# ARDUINO.net
KiCad netlist of a schematic drawn in Altium Designer
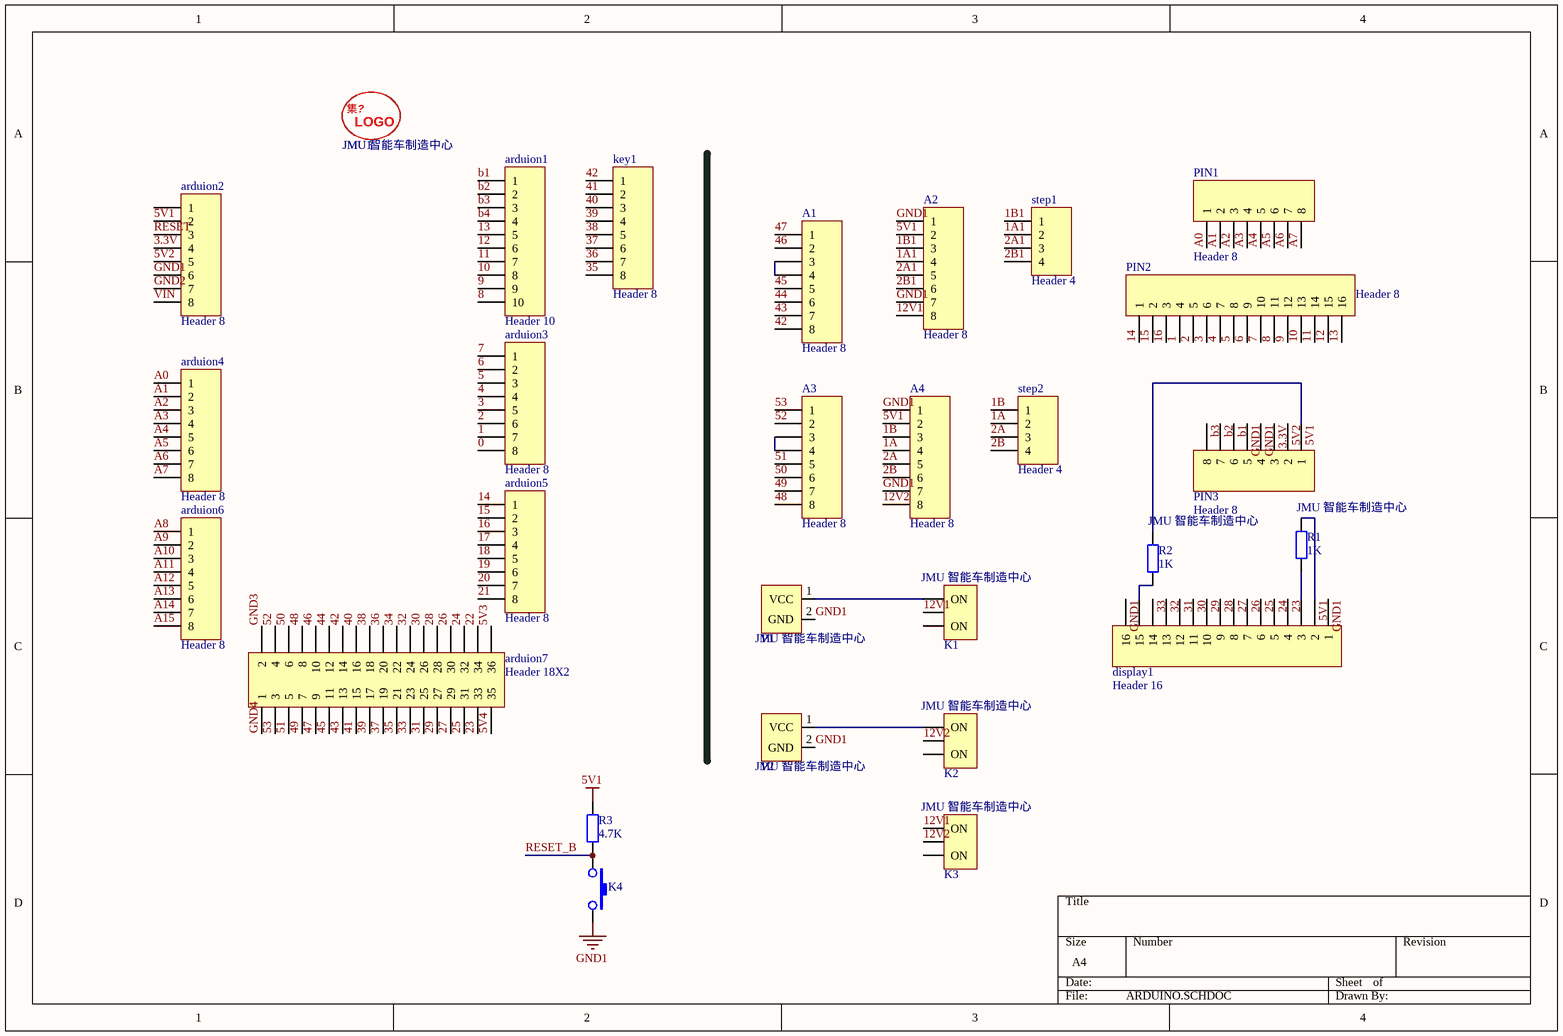
[diagram p0: ARDUINO.SCHDOC]

(export (version "E")
  (design (tool "Eeschema 10.0.6"))
  (components
    (comp (ref "A1")
      (value "Header 8")
      (footprint "HDR1X8")
      (description "Header, 8-Pin")
      (fields (field (name "PUBLISHER") "Altium Limited"))
      (libsource (lib "Miscellaneous Connectors") (part "Header 8"))
    )
    (comp (ref "A2")
      (value "Header 8")
      (footprint "HDR1X8")
      (description "Header, 8-Pin")
      (fields (field (name "PUBLISHER") "Altium Limited"))
      (libsource (lib "Miscellaneous Connectors") (part "Header 8"))
    )
    (comp (ref "A3")
      (value "Header 8")
      (footprint "HDR1X8")
      (description "Header, 8-Pin")
      (fields (field (name "PUBLISHER") "Altium Limited"))
      (libsource (lib "Miscellaneous Connectors") (part "Header 8"))
    )
    (comp (ref "A4")
      (value "Header 8")
      (footprint "HDR1X8")
      (description "Header, 8-Pin")
      (fields (field (name "PUBLISHER") "Altium Limited"))
      (libsource (lib "Miscellaneous Connectors") (part "Header 8"))
    )
    (comp (ref "arduion1")
      (value "Header 10")
      (footprint "HDR1X10")
      (description "Header, 10-Pin")
      (fields (field (name "PUBLISHER") "Altium Limited"))
      (libsource (lib "Miscellaneous Connectors") (part "Header 10"))
    )
    (comp (ref "arduion2")
      (value "Header 8")
      (footprint "HDR1X8")
      (description "Header, 8-Pin")
      (fields (field (name "PUBLISHER") "Altium Limited"))
      (libsource (lib "Miscellaneous Connectors") (part "Header 8"))
    )
    (comp (ref "arduion3")
      (value "Header 8")
      (footprint "HDR1X8")
      (description "Header, 8-Pin")
      (fields (field (name "PUBLISHER") "Altium Limited"))
      (libsource (lib "Miscellaneous Connectors") (part "Header 8"))
    )
    (comp (ref "arduion4")
      (value "Header 8")
      (footprint "HDR1X8")
      (description "Header, 8-Pin")
      (fields (field (name "PUBLISHER") "Altium Limited"))
      (libsource (lib "Miscellaneous Connectors") (part "Header 8"))
    )
    (comp (ref "arduion5")
      (value "Header 8")
      (footprint "HDR1X8")
      (description "Header, 8-Pin")
      (fields (field (name "PUBLISHER") "Altium Limited"))
      (libsource (lib "Miscellaneous Connectors") (part "Header 8"))
    )
    (comp (ref "arduion6")
      (value "Header 8")
      (footprint "HDR1X8")
      (description "Header, 8-Pin")
      (fields (field (name "PUBLISHER") "Altium Limited"))
      (libsource (lib "Miscellaneous Connectors") (part "Header 8"))
    )
    (comp (ref "arduion7")
      (value "Header 18X2")
      (footprint "HDR2X18")
      (description "Header, 18-Pin, Dual row")
      (fields (field (name "PUBLISHER") "Altium Limited"))
      (libsource (lib "Miscellaneous Connectors") (part "Header 18X2"))
    )
    (comp (ref "display1")
      (value "Header 16")
      (footprint "HDR1X16")
      (description "Header, 16-Pin")
      (fields (field (name "PUBLISHER") "Altium Limited"))
      (libsource (lib "Miscellaneous Connectors") (part "Header 16"))
    )
    (comp (ref "JMU1")
      (value "JMU")
      (footprint "JMU_logo（1）")
      (libsource (lib "JMU智能车专用3.0.6") (part "JMU-LOGO"))
    )
    (comp (ref "K1")
      (value "KEY")
      (footprint "钮子开关（大）")
      (description "AC 250V/6A")
      (libsource (lib "JMU智能车专用3.0.6") (part "钮子开关（大）"))
    )
    (comp (ref "K2")
      (value "KEY")
      (footprint "钮子开关（大）")
      (description "AC 250V/6A")
      (libsource (lib "JMU智能车专用3.0.6") (part "钮子开关（大）"))
    )
    (comp (ref "K3")
      (value "KEY")
      (footprint "钮子开关（大）")
      (description "AC 250V/6A")
      (libsource (lib "JMU智能车专用3.0.6") (part "钮子开关（大）"))
    )
    (comp (ref "K4")
      (value "RESET")
      (footprint "SW_PB2_A1")
      (description "按键")
      (libsource (lib "Bigbear") (part "KEY"))
    )
    (comp (ref "key1")
      (value "Header 8")
      (footprint "HDR1X8")
      (description "Header, 8-Pin")
      (fields (field (name "PUBLISHER") "Altium Limited"))
      (libsource (lib "Miscellaneous Connectors") (part "Header 8"))
    )
    (comp (ref "P1")
      (value "T头")
      (footprint "T型接头")
      (description "T型头")
      (libsource (lib "JMU智能车专用3.0.6") (part "电源接线端子"))
    )
    (comp (ref "P2")
      (value "T头")
      (footprint "T型接头")
      (description "T型头")
      (libsource (lib "JMU智能车专用3.0.6") (part "电源接线端子"))
    )
    (comp (ref "PIN1")
      (value "Header 8")
      (footprint "HDR1X8")
      (description "Header, 8-Pin")
      (fields (field (name "PUBLISHER") "Altium Limited"))
      (libsource (lib "") (part "Header 8_1"))
    )
    (comp (ref "PIN2")
      (value "Header 8")
      (footprint "HDR1X16")
      (description "Header, 16-Pin")
      (fields (field (name "PUBLISHER") "Altium Limited"))
      (libsource (lib "") (part "Header 16_1"))
    )
    (comp (ref "PIN3")
      (value "Header 8")
      (footprint "HDR1X8")
      (description "Header, 8-Pin")
      (fields (field (name "PUBLISHER") "Altium Limited"))
      (libsource (lib "") (part "Header 8_2"))
    )
    (comp (ref "R1")
      (value "1K")
      (footprint "0603")
      (description "通用电阻")
      (libsource (lib "JMU智能车专用3.0.6") (part "Res"))
    )
    (comp (ref "R2")
      (value "1K")
      (footprint "0603")
      (description "通用电阻")
      (libsource (lib "JMU智能车专用3.0.6") (part "Res"))
    )
    (comp (ref "R3") (value "4.7K") (footprint "0603-r") (libsource (lib "Bigbear") (part "RES")))
    (comp (ref "step1")
      (value "Header 4")
      (footprint "HDR1X4")
      (description "Header, 4-Pin")
      (fields (field (name "PUBLISHER") "Altium Limited"))
      (libsource (lib "Miscellaneous Connectors") (part "Header 4"))
    )
    (comp (ref "step2")
      (value "Header 4")
      (footprint "HDR1X4")
      (description "Header, 4-Pin")
      (fields (field (name "PUBLISHER") "Altium Limited"))
      (libsource (lib "Miscellaneous Connectors") (part "Header 4"))
    )
  )
  (nets
    (net (code "1") (name "/0") (class "Default")
      (node (ref "arduion3") (pin "8") (pinfunction "8_8") (pintype "passive"))
    )
    (net (code "2") (name "/1") (class "Default")
      (node (ref "PIN2") (pin "4") (pinfunction "4_4") (pintype "passive"))
      (node (ref "arduion3") (pin "7") (pinfunction "7_7") (pintype "passive"))
    )
    (net (code "3") (name "/1A") (class "Default")
      (node (ref "A4") (pin "4") (pinfunction "4_4") (pintype "passive"))
      (node (ref "step2") (pin "2") (pinfunction "2_2") (pintype "passive"))
    )
    (net (code "4") (name "/1A1") (class "Default")
      (node (ref "A2") (pin "4") (pinfunction "4_4") (pintype "passive"))
      (node (ref "step1") (pin "2") (pinfunction "2_2") (pintype "passive"))
    )
    (net (code "5") (name "/1B") (class "Default")
      (node (ref "A4") (pin "3") (pinfunction "3_3") (pintype "passive"))
      (node (ref "step2") (pin "1") (pinfunction "1_1") (pintype "passive"))
    )
    (net (code "6") (name "/1B1") (class "Default")
      (node (ref "A2") (pin "3") (pinfunction "3_3") (pintype "passive"))
      (node (ref "step1") (pin "1") (pinfunction "1_1") (pintype "passive"))
    )
    (net (code "7") (name "/2") (class "Default")
      (node (ref "PIN2") (pin "5") (pinfunction "5_5") (pintype "passive"))
      (node (ref "arduion3") (pin "6") (pinfunction "6_6") (pintype "passive"))
    )
    (net (code "8") (name "/2A") (class "Default")
      (node (ref "A4") (pin "5") (pinfunction "5_5") (pintype "passive"))
      (node (ref "step2") (pin "3") (pinfunction "3_3") (pintype "passive"))
    )
    (net (code "9") (name "/2A1") (class "Default")
      (node (ref "A2") (pin "5") (pinfunction "5_5") (pintype "passive"))
      (node (ref "step1") (pin "3") (pinfunction "3_3") (pintype "passive"))
    )
    (net (code "10") (name "/2B") (class "Default")
      (node (ref "A4") (pin "6") (pinfunction "6_6") (pintype "passive"))
      (node (ref "step2") (pin "4") (pinfunction "4_4") (pintype "passive"))
    )
    (net (code "11") (name "/2B1") (class "Default")
      (node (ref "A2") (pin "6") (pinfunction "6_6") (pintype "passive"))
      (node (ref "step1") (pin "4") (pinfunction "4_4") (pintype "passive"))
    )
    (net (code "12") (name "/3") (class "Default")
      (node (ref "PIN2") (pin "6") (pinfunction "6_6") (pintype "passive"))
      (node (ref "arduion3") (pin "5") (pinfunction "5_5") (pintype "passive"))
    )
    (net (code "13") (name "/3.3V") (class "Default")
      (node (ref "PIN3") (pin "3") (pinfunction "3_3") (pintype "passive"))
      (node (ref "arduion2") (pin "4") (pinfunction "4_4") (pintype "passive"))
    )
    (net (code "14") (name "/4") (class "Default")
      (node (ref "PIN2") (pin "7") (pinfunction "7_7") (pintype "passive"))
      (node (ref "arduion3") (pin "4") (pinfunction "4_4") (pintype "passive"))
    )
    (net (code "15") (name "/5") (class "Default")
      (node (ref "PIN2") (pin "8") (pinfunction "8_8") (pintype "passive"))
      (node (ref "arduion3") (pin "3") (pinfunction "3_3") (pintype "passive"))
    )
    (net (code "16") (name "/5V2") (class "Default")
      (node (ref "PIN3") (pin "2") (pinfunction "2_2") (pintype "passive"))
      (node (ref "arduion2") (pin "5") (pinfunction "5_5") (pintype "passive"))
    )
    (net (code "17") (name "/5V3") (class "Default")
      (node (ref "arduion7") (pin "36") (pinfunction "36_36") (pintype "passive"))
    )
    (net (code "18") (name "/5V4") (class "Default")
      (node (ref "arduion7") (pin "35") (pinfunction "35_35") (pintype "passive"))
    )
    (net (code "19") (name "/6") (class "Default")
      (node (ref "PIN2") (pin "9") (pinfunction "9_9") (pintype "passive"))
      (node (ref "arduion3") (pin "2") (pinfunction "2_2") (pintype "passive"))
    )
    (net (code "20") (name "/7") (class "Default")
      (node (ref "PIN2") (pin "10") (pinfunction "10_10") (pintype "passive"))
      (node (ref "arduion3") (pin "1") (pinfunction "1_1") (pintype "passive"))
    )
    (net (code "21") (name "/8") (class "Default")
      (node (ref "PIN2") (pin "11") (pinfunction "11_11") (pintype "passive"))
      (node (ref "arduion1") (pin "10") (pinfunction "10_10") (pintype "passive"))
    )
    (net (code "22") (name "/9") (class "Default")
      (node (ref "PIN2") (pin "12") (pinfunction "12_12") (pintype "passive"))
      (node (ref "arduion1") (pin "9") (pinfunction "9_9") (pintype "passive"))
    )
    (net (code "23") (name "/10") (class "Default")
      (node (ref "PIN2") (pin "13") (pinfunction "13_13") (pintype "passive"))
      (node (ref "arduion1") (pin "8") (pinfunction "8_8") (pintype "passive"))
    )
    (net (code "24") (name "/11") (class "Default")
      (node (ref "PIN2") (pin "14") (pinfunction "14_14") (pintype "passive"))
      (node (ref "arduion1") (pin "7") (pinfunction "7_7") (pintype "passive"))
    )
    (net (code "25") (name "/12") (class "Default")
      (node (ref "PIN2") (pin "15") (pinfunction "15_15") (pintype "passive"))
      (node (ref "arduion1") (pin "6") (pinfunction "6_6") (pintype "passive"))
    )
    (net (code "26") (name "/12V1") (class "Default")
      (node (ref "A2") (pin "8") (pinfunction "8_8") (pintype "passive"))
      (node (ref "K1") (pin "2") (pinfunction "com_2") (pintype "passive"))
      (node (ref "K3") (pin "1") (pinfunction "ON_1") (pintype "passive"))
    )
    (net (code "27") (name "/12V2") (class "Default")
      (node (ref "A4") (pin "8") (pinfunction "8_8") (pintype "passive"))
      (node (ref "K2") (pin "2") (pinfunction "com_2") (pintype "passive"))
      (node (ref "K3") (pin "2") (pinfunction "com_2") (pintype "passive"))
    )
    (net (code "28") (name "/13") (class "Default")
      (node (ref "PIN2") (pin "16") (pinfunction "16_16") (pintype "passive"))
      (node (ref "arduion1") (pin "5") (pinfunction "5_5") (pintype "passive"))
    )
    (net (code "29") (name "/14") (class "Default")
      (node (ref "PIN2") (pin "1") (pinfunction "1_1") (pintype "passive"))
      (node (ref "arduion5") (pin "1") (pinfunction "1_1") (pintype "passive"))
    )
    (net (code "30") (name "/15") (class "Default")
      (node (ref "PIN2") (pin "2") (pinfunction "2_2") (pintype "passive"))
      (node (ref "arduion5") (pin "2") (pinfunction "2_2") (pintype "passive"))
    )
    (net (code "31") (name "/16") (class "Default")
      (node (ref "PIN2") (pin "3") (pinfunction "3_3") (pintype "passive"))
      (node (ref "arduion5") (pin "3") (pinfunction "3_3") (pintype "passive"))
    )
    (net (code "32") (name "/17") (class "Default")
      (node (ref "arduion5") (pin "4") (pinfunction "4_4") (pintype "passive"))
    )
    (net (code "33") (name "/18") (class "Default")
      (node (ref "arduion5") (pin "5") (pinfunction "5_5") (pintype "passive"))
    )
    (net (code "34") (name "/19") (class "Default")
      (node (ref "arduion5") (pin "6") (pinfunction "6_6") (pintype "passive"))
    )
    (net (code "35") (name "/20") (class "Default")
      (node (ref "arduion5") (pin "7") (pinfunction "7_7") (pintype "passive"))
    )
    (net (code "36") (name "/21") (class "Default")
      (node (ref "arduion5") (pin "8") (pinfunction "8_8") (pintype "passive"))
    )
    (net (code "37") (name "/22") (class "Default")
      (node (ref "arduion7") (pin "34") (pinfunction "34_34") (pintype "passive"))
    )
    (net (code "38") (name "/23") (class "Default")
      (node (ref "arduion7") (pin "33") (pinfunction "33_33") (pintype "passive"))
      (node (ref "display1") (pin "4") (pinfunction "4_4") (pintype "passive"))
    )
    (net (code "39") (name "/24") (class "Default")
      (node (ref "arduion7") (pin "32") (pinfunction "32_32") (pintype "passive"))
      (node (ref "display1") (pin "5") (pinfunction "5_5") (pintype "passive"))
    )
    (net (code "40") (name "/25") (class "Default")
      (node (ref "arduion7") (pin "31") (pinfunction "31_31") (pintype "passive"))
      (node (ref "display1") (pin "6") (pinfunction "6_6") (pintype "passive"))
    )
    (net (code "41") (name "/26") (class "Default")
      (node (ref "arduion7") (pin "30") (pinfunction "30_30") (pintype "passive"))
      (node (ref "display1") (pin "7") (pinfunction "7_7") (pintype "passive"))
    )
    (net (code "42") (name "/27") (class "Default")
      (node (ref "arduion7") (pin "29") (pinfunction "29_29") (pintype "passive"))
      (node (ref "display1") (pin "8") (pinfunction "8_8") (pintype "passive"))
    )
    (net (code "43") (name "/28") (class "Default")
      (node (ref "arduion7") (pin "28") (pinfunction "28_28") (pintype "passive"))
      (node (ref "display1") (pin "9") (pinfunction "9_9") (pintype "passive"))
    )
    (net (code "44") (name "/29") (class "Default")
      (node (ref "arduion7") (pin "27") (pinfunction "27_27") (pintype "passive"))
      (node (ref "display1") (pin "10") (pinfunction "10_10") (pintype "passive"))
    )
    (net (code "45") (name "/30") (class "Default")
      (node (ref "arduion7") (pin "26") (pinfunction "26_26") (pintype "passive"))
      (node (ref "display1") (pin "11") (pinfunction "11_11") (pintype "passive"))
    )
    (net (code "46") (name "/31") (class "Default")
      (node (ref "arduion7") (pin "25") (pinfunction "25_25") (pintype "passive"))
      (node (ref "display1") (pin "12") (pinfunction "12_12") (pintype "passive"))
    )
    (net (code "47") (name "/32") (class "Default")
      (node (ref "arduion7") (pin "24") (pinfunction "24_24") (pintype "passive"))
      (node (ref "display1") (pin "13") (pinfunction "13_13") (pintype "passive"))
    )
    (net (code "48") (name "/33") (class "Default")
      (node (ref "arduion7") (pin "23") (pinfunction "23_23") (pintype "passive"))
      (node (ref "display1") (pin "14") (pinfunction "14_14") (pintype "passive"))
    )
    (net (code "49") (name "/34") (class "Default")
      (node (ref "arduion7") (pin "22") (pinfunction "22_22") (pintype "passive"))
    )
    (net (code "50") (name "/35") (class "Default")
      (node (ref "arduion7") (pin "21") (pinfunction "21_21") (pintype "passive"))
      (node (ref "key1") (pin "8") (pinfunction "8_8") (pintype "passive"))
    )
    (net (code "51") (name "/36") (class "Default")
      (node (ref "arduion7") (pin "20") (pinfunction "20_20") (pintype "passive"))
      (node (ref "key1") (pin "7") (pinfunction "7_7") (pintype "passive"))
    )
    (net (code "52") (name "/37") (class "Default")
      (node (ref "arduion7") (pin "19") (pinfunction "19_19") (pintype "passive"))
      (node (ref "key1") (pin "6") (pinfunction "6_6") (pintype "passive"))
    )
    (net (code "53") (name "/38") (class "Default")
      (node (ref "arduion7") (pin "18") (pinfunction "18_18") (pintype "passive"))
      (node (ref "key1") (pin "5") (pinfunction "5_5") (pintype "passive"))
    )
    (net (code "54") (name "/39") (class "Default")
      (node (ref "arduion7") (pin "17") (pinfunction "17_17") (pintype "passive"))
      (node (ref "key1") (pin "4") (pinfunction "4_4") (pintype "passive"))
    )
    (net (code "55") (name "/40") (class "Default")
      (node (ref "arduion7") (pin "16") (pinfunction "16_16") (pintype "passive"))
      (node (ref "key1") (pin "3") (pinfunction "3_3") (pintype "passive"))
    )
    (net (code "56") (name "/41") (class "Default")
      (node (ref "arduion7") (pin "15") (pinfunction "15_15") (pintype "passive"))
      (node (ref "key1") (pin "2") (pinfunction "2_2") (pintype "passive"))
    )
    (net (code "57") (name "/42") (class "Default")
      (node (ref "A1") (pin "8") (pinfunction "8_8") (pintype "passive"))
      (node (ref "arduion7") (pin "14") (pinfunction "14_14") (pintype "passive"))
      (node (ref "key1") (pin "1") (pinfunction "1_1") (pintype "passive"))
    )
    (net (code "58") (name "/43") (class "Default")
      (node (ref "A1") (pin "7") (pinfunction "7_7") (pintype "passive"))
      (node (ref "arduion7") (pin "13") (pinfunction "13_13") (pintype "passive"))
    )
    (net (code "59") (name "/44") (class "Default")
      (node (ref "A1") (pin "6") (pinfunction "6_6") (pintype "passive"))
      (node (ref "arduion7") (pin "12") (pinfunction "12_12") (pintype "passive"))
    )
    (net (code "60") (name "/45") (class "Default")
      (node (ref "A1") (pin "5") (pinfunction "5_5") (pintype "passive"))
      (node (ref "arduion7") (pin "11") (pinfunction "11_11") (pintype "passive"))
    )
    (net (code "61") (name "/46") (class "Default")
      (node (ref "A1") (pin "2") (pinfunction "2_2") (pintype "passive"))
      (node (ref "arduion7") (pin "10") (pinfunction "10_10") (pintype "passive"))
    )
    (net (code "62") (name "/47") (class "Default")
      (node (ref "A1") (pin "1") (pinfunction "1_1") (pintype "passive"))
      (node (ref "arduion7") (pin "9") (pinfunction "9_9") (pintype "passive"))
    )
    (net (code "63") (name "/48") (class "Default")
      (node (ref "A3") (pin "8") (pinfunction "8_8") (pintype "passive"))
      (node (ref "arduion7") (pin "8") (pinfunction "8_8") (pintype "passive"))
    )
    (net (code "64") (name "/49") (class "Default")
      (node (ref "A3") (pin "7") (pinfunction "7_7") (pintype "passive"))
      (node (ref "arduion7") (pin "7") (pinfunction "7_7") (pintype "passive"))
    )
    (net (code "65") (name "/50") (class "Default")
      (node (ref "A3") (pin "6") (pinfunction "6_6") (pintype "passive"))
      (node (ref "arduion7") (pin "6") (pinfunction "6_6") (pintype "passive"))
    )
    (net (code "66") (name "/51") (class "Default")
      (node (ref "A3") (pin "5") (pinfunction "5_5") (pintype "passive"))
      (node (ref "arduion7") (pin "5") (pinfunction "5_5") (pintype "passive"))
    )
    (net (code "67") (name "/52") (class "Default")
      (node (ref "A3") (pin "2") (pinfunction "2_2") (pintype "passive"))
      (node (ref "arduion7") (pin "4") (pinfunction "4_4") (pintype "passive"))
    )
    (net (code "68") (name "/53") (class "Default")
      (node (ref "A3") (pin "1") (pinfunction "1_1") (pintype "passive"))
      (node (ref "arduion7") (pin "3") (pinfunction "3_3") (pintype "passive"))
    )
    (net (code "69") (name "/A0") (class "Default")
      (node (ref "PIN1") (pin "1") (pinfunction "1_1") (pintype "passive"))
      (node (ref "arduion4") (pin "1") (pinfunction "1_1") (pintype "passive"))
    )
    (net (code "70") (name "/A1") (class "Default")
      (node (ref "PIN1") (pin "2") (pinfunction "2_2") (pintype "passive"))
      (node (ref "arduion4") (pin "2") (pinfunction "2_2") (pintype "passive"))
    )
    (net (code "71") (name "/A2") (class "Default")
      (node (ref "PIN1") (pin "3") (pinfunction "3_3") (pintype "passive"))
      (node (ref "arduion4") (pin "3") (pinfunction "3_3") (pintype "passive"))
    )
    (net (code "72") (name "/A3") (class "Default")
      (node (ref "PIN1") (pin "4") (pinfunction "4_4") (pintype "passive"))
      (node (ref "arduion4") (pin "4") (pinfunction "4_4") (pintype "passive"))
    )
    (net (code "73") (name "/A4") (class "Default")
      (node (ref "PIN1") (pin "5") (pinfunction "5_5") (pintype "passive"))
      (node (ref "arduion4") (pin "5") (pinfunction "5_5") (pintype "passive"))
    )
    (net (code "74") (name "/A5") (class "Default")
      (node (ref "PIN1") (pin "6") (pinfunction "6_6") (pintype "passive"))
      (node (ref "arduion4") (pin "6") (pinfunction "6_6") (pintype "passive"))
    )
    (net (code "75") (name "/A6") (class "Default")
      (node (ref "PIN1") (pin "7") (pinfunction "7_7") (pintype "passive"))
      (node (ref "arduion4") (pin "7") (pinfunction "7_7") (pintype "passive"))
    )
    (net (code "76") (name "/A7") (class "Default")
      (node (ref "PIN1") (pin "8") (pinfunction "8_8") (pintype "passive"))
      (node (ref "arduion4") (pin "8") (pinfunction "8_8") (pintype "passive"))
    )
    (net (code "77") (name "/A8") (class "Default")
      (node (ref "arduion6") (pin "1") (pinfunction "1_1") (pintype "passive"))
    )
    (net (code "78") (name "/A9") (class "Default")
      (node (ref "arduion6") (pin "2") (pinfunction "2_2") (pintype "passive"))
    )
    (net (code "79") (name "/A10") (class "Default")
      (node (ref "arduion6") (pin "3") (pinfunction "3_3") (pintype "passive"))
    )
    (net (code "80") (name "/A11") (class "Default")
      (node (ref "arduion6") (pin "4") (pinfunction "4_4") (pintype "passive"))
    )
    (net (code "81") (name "/A12") (class "Default")
      (node (ref "arduion6") (pin "5") (pinfunction "5_5") (pintype "passive"))
    )
    (net (code "82") (name "/A13") (class "Default")
      (node (ref "arduion6") (pin "6") (pinfunction "6_6") (pintype "passive"))
    )
    (net (code "83") (name "/A14") (class "Default")
      (node (ref "arduion6") (pin "7") (pinfunction "7_7") (pintype "passive"))
    )
    (net (code "84") (name "/A15") (class "Default")
      (node (ref "arduion6") (pin "8") (pinfunction "8_8") (pintype "passive"))
    )
    (net (code "85") (name "/GND2") (class "Default")
      (node (ref "arduion2") (pin "7") (pinfunction "7_7") (pintype "passive"))
    )
    (net (code "86") (name "/GND3") (class "Default")
      (node (ref "arduion7") (pin "2") (pinfunction "2_2") (pintype "passive"))
    )
    (net (code "87") (name "/GND4") (class "Default")
      (node (ref "arduion7") (pin "1") (pinfunction "1_1") (pintype "passive"))
    )
    (net (code "88") (name "/RESET") (class "Default")
      (node (ref "arduion2") (pin "3") (pinfunction "3_3") (pintype "passive"))
    )
    (net (code "89") (name "/RESET_B") (class "Default")
      (node (ref "K4") (pin "1") (pinfunction "1_1") (pintype "passive"))
      (node (ref "R3") (pin "1") (pinfunction "1_1") (pintype "passive"))
    )
    (net (code "90") (name "/VIN") (class "Default")
      (node (ref "arduion2") (pin "8") (pinfunction "8_8") (pintype "passive"))
    )
    (net (code "91") (name "/b1") (class "Default")
      (node (ref "PIN3") (pin "6") (pinfunction "6_6") (pintype "passive"))
      (node (ref "arduion1") (pin "1") (pinfunction "1_1") (pintype "passive"))
    )
    (net (code "92") (name "/b2") (class "Default")
      (node (ref "PIN3") (pin "7") (pinfunction "7_7") (pintype "passive"))
      (node (ref "arduion1") (pin "2") (pinfunction "2_2") (pintype "passive"))
    )
    (net (code "93") (name "/b3") (class "Default")
      (node (ref "PIN3") (pin "8") (pinfunction "8_8") (pintype "passive"))
      (node (ref "arduion1") (pin "3") (pinfunction "3_3") (pintype "passive"))
    )
    (net (code "94") (name "/b4") (class "Default")
      (node (ref "arduion1") (pin "4") (pinfunction "4_4") (pintype "passive"))
    )
    (net (code "95") (name "5V1") (class "Default")
      (node (ref "A2") (pin "2") (pinfunction "2_2") (pintype "passive"))
      (node (ref "A4") (pin "2") (pinfunction "2_2") (pintype "passive"))
      (node (ref "PIN3") (pin "1") (pinfunction "1_1") (pintype "passive"))
      (node (ref "R1") (pin "2") (pinfunction "2_2") (pintype "passive"))
      (node (ref "R2") (pin "2") (pinfunction "2_2") (pintype "passive"))
      (node (ref "R3") (pin "2") (pinfunction "2_2") (pintype "passive"))
      (node (ref "arduion2") (pin "2") (pinfunction "2_2") (pintype "passive"))
      (node (ref "display1") (pin "2") (pinfunction "2_2") (pintype "passive"))
    )
    (net (code "96") (name "GND1") (class "Default")
      (node (ref "A2") (pin "1") (pinfunction "1_1") (pintype "passive"))
      (node (ref "A2") (pin "7") (pinfunction "7_7") (pintype "passive"))
      (node (ref "A4") (pin "1") (pinfunction "1_1") (pintype "passive"))
      (node (ref "A4") (pin "7") (pinfunction "7_7") (pintype "passive"))
      (node (ref "K4") (pin "2") (pinfunction "2_2") (pintype "passive"))
      (node (ref "P1") (pin "2") (pinfunction "GND_2") (pintype "passive"))
      (node (ref "P2") (pin "2") (pinfunction "GND_2") (pintype "passive"))
      (node (ref "PIN3") (pin "4") (pinfunction "4_4") (pintype "passive"))
      (node (ref "PIN3") (pin "5") (pinfunction "5_5") (pintype "passive"))
      (node (ref "arduion2") (pin "6") (pinfunction "6_6") (pintype "passive"))
      (node (ref "display1") (pin "1") (pinfunction "1_1") (pintype "passive"))
      (node (ref "display1") (pin "16") (pinfunction "16_16") (pintype "passive"))
    )
    (net (code "97") (name "Net-(A1-Pad3)") (class "Default")
      (node (ref "A1") (pin "3") (pinfunction "3_3") (pintype "passive"))
      (node (ref "A1") (pin "4") (pinfunction "4_4") (pintype "passive"))
    )
    (net (code "98") (name "Net-(A3-Pad3)") (class "Default")
      (node (ref "A3") (pin "3") (pinfunction "3_3") (pintype "passive"))
      (node (ref "A3") (pin "4") (pinfunction "4_4") (pintype "passive"))
    )
    (net (code "99") (name "Net-(P1-VCC)") (class "Default")
      (node (ref "K1") (pin "1") (pinfunction "ON_1") (pintype "passive"))
      (node (ref "P1") (pin "1") (pinfunction "VCC_1") (pintype "passive"))
    )
    (net (code "100") (name "Net-(P2-VCC)") (class "Default")
      (node (ref "K2") (pin "1") (pinfunction "ON_1") (pintype "passive"))
      (node (ref "P2") (pin "1") (pinfunction "VCC_1") (pintype "passive"))
    )
    (net (code "101") (name "Net-(R1-Pad1)") (class "Default")
      (node (ref "R1") (pin "1") (pinfunction "1_1") (pintype "passive"))
      (node (ref "display1") (pin "3") (pinfunction "3_3") (pintype "passive"))
    )
    (net (code "102") (name "Net-(R2-Pad1)") (class "Default")
      (node (ref "R2") (pin "1") (pinfunction "1_1") (pintype "passive"))
      (node (ref "display1") (pin "15") (pinfunction "15_15") (pintype "passive"))
    )
    (net (code "103") (name "unconnected-(K1-ON-Pad3)") (class "Default")
      (node (ref "K1") (pin "3") (pinfunction "ON_3") (pintype "passive"))
    )
    (net (code "104") (name "unconnected-(K2-ON-Pad3)") (class "Default")
      (node (ref "K2") (pin "3") (pinfunction "ON_3") (pintype "passive"))
    )
    (net (code "105") (name "unconnected-(K3-ON-Pad3)") (class "Default")
      (node (ref "K3") (pin "3") (pinfunction "ON_3") (pintype "passive"))
    )
    (net (code "106") (name "unconnected-(arduion2-Pad1)") (class "Default")
      (node (ref "arduion2") (pin "1") (pinfunction "1_1") (pintype "passive"))
    )
  )
)
